# untitled.net
KiCad netlist of a schematic drawn in EAGLE
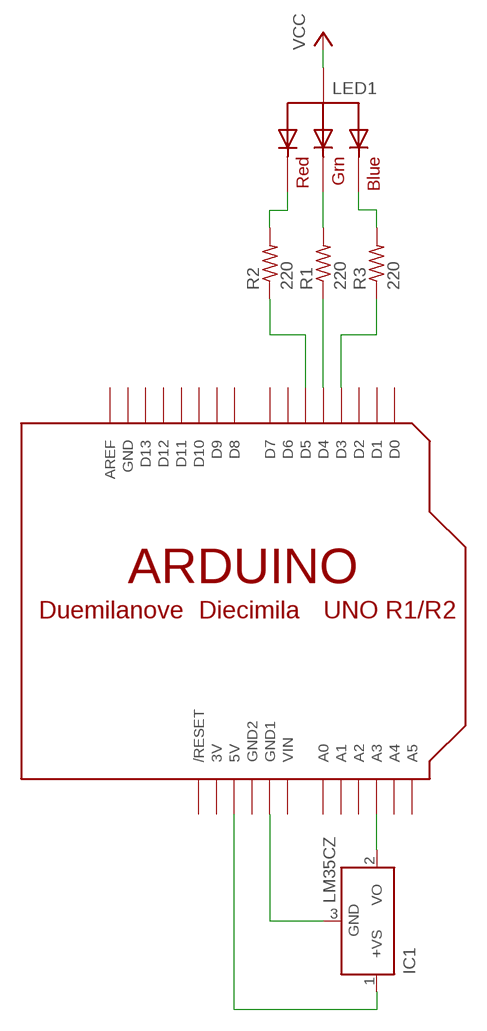
[diagram p0: schematic, sheet 1]

(export (version "E")
  (design (tool "Eeschema 10.0.6"))
  (components
    (comp (ref "IC1")
      (value "LM35CZ")
      (footprint "eagle-import:TO92")
      (libsource (lib "eagle-import") (part "LM35CZ"))
    )
    (comp (ref "LED1")
      (value "RGBLED_CA-5MM")
      (footprint "eagle-import:LED5MMRGB")
      (libsource (lib "eagle-import") (part "RGBLED_CA-5MM"))
    )
    (comp (ref "R1")
      (value "220")
      (footprint "eagle-import:0204_5")
      (libsource (lib "eagle-import") (part "R-US_0204/5"))
    )
    (comp (ref "R2")
      (value "220")
      (footprint "eagle-import:0204_5")
      (libsource (lib "eagle-import") (part "R-US_0204/5"))
    )
    (comp (ref "R3")
      (value "220")
      (footprint "eagle-import:0204_5")
      (libsource (lib "eagle-import") (part "R-US_0204/5"))
    )
    (comp (ref "U$1")
      (value "ARDUINOUNO")
      (footprint "eagle-import:ARDUINO")
      (libsource (lib "eagle-import") (part "ARDUINOUNO"))
    )
  )
  (nets
    (net (code "1") (name "/3V") (class "Default")
      (node (ref "U$1") (pin "3V") (pinfunction "3V_3V") (pintype "power_in"))
    )
    (net (code "2") (name "/GND") (class "Default")
      (node (ref "U$1") (pin "GND") (pinfunction "GND_GND") (pintype "power_in"))
    )
    (net (code "3") (name "/GND2") (class "Default")
      (node (ref "U$1") (pin "GND2") (pinfunction "GND2_GND2") (pintype "power_in"))
    )
    (net (code "4") (name "/VIN") (class "Default")
      (node (ref "U$1") (pin "VIN") (pinfunction "VIN_VIN") (pintype "power_in"))
    )
    (net (code "5") (name "Net-(IC1-+VS)") (class "Default")
      (node (ref "IC1") (pin "1") (pinfunction "+VS_1") (pintype "input"))
      (node (ref "U$1") (pin "5V") (pinfunction "5V_5V") (pintype "power_in"))
    )
    (net (code "6") (name "Net-(IC1-GND)") (class "Default")
      (node (ref "IC1") (pin "3") (pinfunction "GND_3") (pintype "power_in"))
      (node (ref "U$1") (pin "GND1") (pinfunction "GND1_GND1") (pintype "power_in"))
    )
    (net (code "7") (name "Net-(IC1-VO)") (class "Default")
      (node (ref "IC1") (pin "2") (pinfunction "VO_2") (pintype "input"))
      (node (ref "U$1") (pin "A3") (pinfunction "A3_A3") (pintype "bidirectional"))
    )
    (net (code "8") (name "Net-(LED1-BLUE)") (class "Default")
      (node (ref "LED1") (pin "4") (pinfunction "BLUE_4") (pintype "bidirectional"))
      (node (ref "R3") (pin "2") (pinfunction "2_2") (pintype "passive"))
    )
    (net (code "9") (name "Net-(LED1-GREEN)") (class "Default")
      (node (ref "LED1") (pin "3") (pinfunction "GREEN_3") (pintype "bidirectional"))
      (node (ref "R1") (pin "2") (pinfunction "2_2") (pintype "passive"))
    )
    (net (code "10") (name "Net-(LED1-RED)") (class "Default")
      (node (ref "LED1") (pin "1") (pinfunction "RED_1") (pintype "bidirectional"))
      (node (ref "R2") (pin "2") (pinfunction "2_2") (pintype "passive"))
    )
    (net (code "11") (name "Net-(R1-Pad1)") (class "Default")
      (node (ref "R1") (pin "1") (pinfunction "1_1") (pintype "passive"))
      (node (ref "U$1") (pin "D4") (pinfunction "D4_D4") (pintype "bidirectional"))
    )
    (net (code "12") (name "Net-(R2-Pad1)") (class "Default")
      (node (ref "R2") (pin "1") (pinfunction "1_1") (pintype "passive"))
      (node (ref "U$1") (pin "D5") (pinfunction "D5_D5") (pintype "bidirectional"))
    )
    (net (code "13") (name "Net-(R3-Pad1)") (class "Default")
      (node (ref "R3") (pin "1") (pinfunction "1_1") (pintype "passive"))
      (node (ref "U$1") (pin "D3") (pinfunction "D3_D3") (pintype "bidirectional"))
    )
    (net (code "14") (name "VCC") (class "Default")
      (node (ref "LED1") (pin "2") (pinfunction "VCC_2") (pintype "bidirectional"))
    )
    (net (code "15") (name "unconnected-(U$1-PadA0)") (class "Default")
      (node (ref "U$1") (pin "A0") (pinfunction "A0_A0") (pintype "bidirectional"))
    )
    (net (code "16") (name "unconnected-(U$1-PadA1)") (class "Default")
      (node (ref "U$1") (pin "A1") (pinfunction "A1_A1") (pintype "bidirectional"))
    )
    (net (code "17") (name "unconnected-(U$1-PadA2)") (class "Default")
      (node (ref "U$1") (pin "A2") (pinfunction "A2_A2") (pintype "bidirectional"))
    )
    (net (code "18") (name "unconnected-(U$1-PadA4)") (class "Default")
      (node (ref "U$1") (pin "A4") (pinfunction "A4_A4") (pintype "bidirectional"))
    )
    (net (code "19") (name "unconnected-(U$1-PadA5)") (class "Default")
      (node (ref "U$1") (pin "A5") (pinfunction "A5_A5") (pintype "bidirectional"))
    )
    (net (code "20") (name "unconnected-(U$1-PadAREF)") (class "Default")
      (node (ref "U$1") (pin "AREF") (pinfunction "AREF_AREF") (pintype "bidirectional"))
    )
    (net (code "21") (name "unconnected-(U$1-PadD0)") (class "Default")
      (node (ref "U$1") (pin "D0") (pinfunction "D0_D0") (pintype "bidirectional"))
    )
    (net (code "22") (name "unconnected-(U$1-PadD1)") (class "Default")
      (node (ref "U$1") (pin "D1") (pinfunction "D1_D1") (pintype "bidirectional"))
    )
    (net (code "23") (name "unconnected-(U$1-PadD2)") (class "Default")
      (node (ref "U$1") (pin "D2") (pinfunction "D2_D2") (pintype "bidirectional"))
    )
    (net (code "24") (name "unconnected-(U$1-PadD6)") (class "Default")
      (node (ref "U$1") (pin "D6") (pinfunction "D6_D6") (pintype "bidirectional"))
    )
    (net (code "25") (name "unconnected-(U$1-PadD7)") (class "Default")
      (node (ref "U$1") (pin "D7") (pinfunction "D7_D7") (pintype "bidirectional"))
    )
    (net (code "26") (name "unconnected-(U$1-PadD8)") (class "Default")
      (node (ref "U$1") (pin "D8") (pinfunction "D8_D8") (pintype "bidirectional"))
    )
    (net (code "27") (name "unconnected-(U$1-PadD9)") (class "Default")
      (node (ref "U$1") (pin "D9") (pinfunction "D9_D9") (pintype "bidirectional"))
    )
    (net (code "28") (name "unconnected-(U$1-PadD10)") (class "Default")
      (node (ref "U$1") (pin "D10") (pinfunction "D10_D10") (pintype "bidirectional"))
    )
    (net (code "29") (name "unconnected-(U$1-PadD11)") (class "Default")
      (node (ref "U$1") (pin "D11") (pinfunction "D11_D11") (pintype "bidirectional"))
    )
    (net (code "30") (name "unconnected-(U$1-PadD12)") (class "Default")
      (node (ref "U$1") (pin "D12") (pinfunction "D12_D12") (pintype "bidirectional"))
    )
    (net (code "31") (name "unconnected-(U$1-PadD13)") (class "Default")
      (node (ref "U$1") (pin "D13") (pinfunction "D13_D13") (pintype "bidirectional"))
    )
    (net (code "32") (name "unconnected-(U$1-{slash}RESET-PadRESET)") (class "Default")
      (node (ref "U$1") (pin "RESET") (pinfunction "/RESET_RESET") (pintype "bidirectional"))
    )
  )
)
